# ESP32-S3_module.net
KiCad netlist of a schematic drawn in Altium Designer
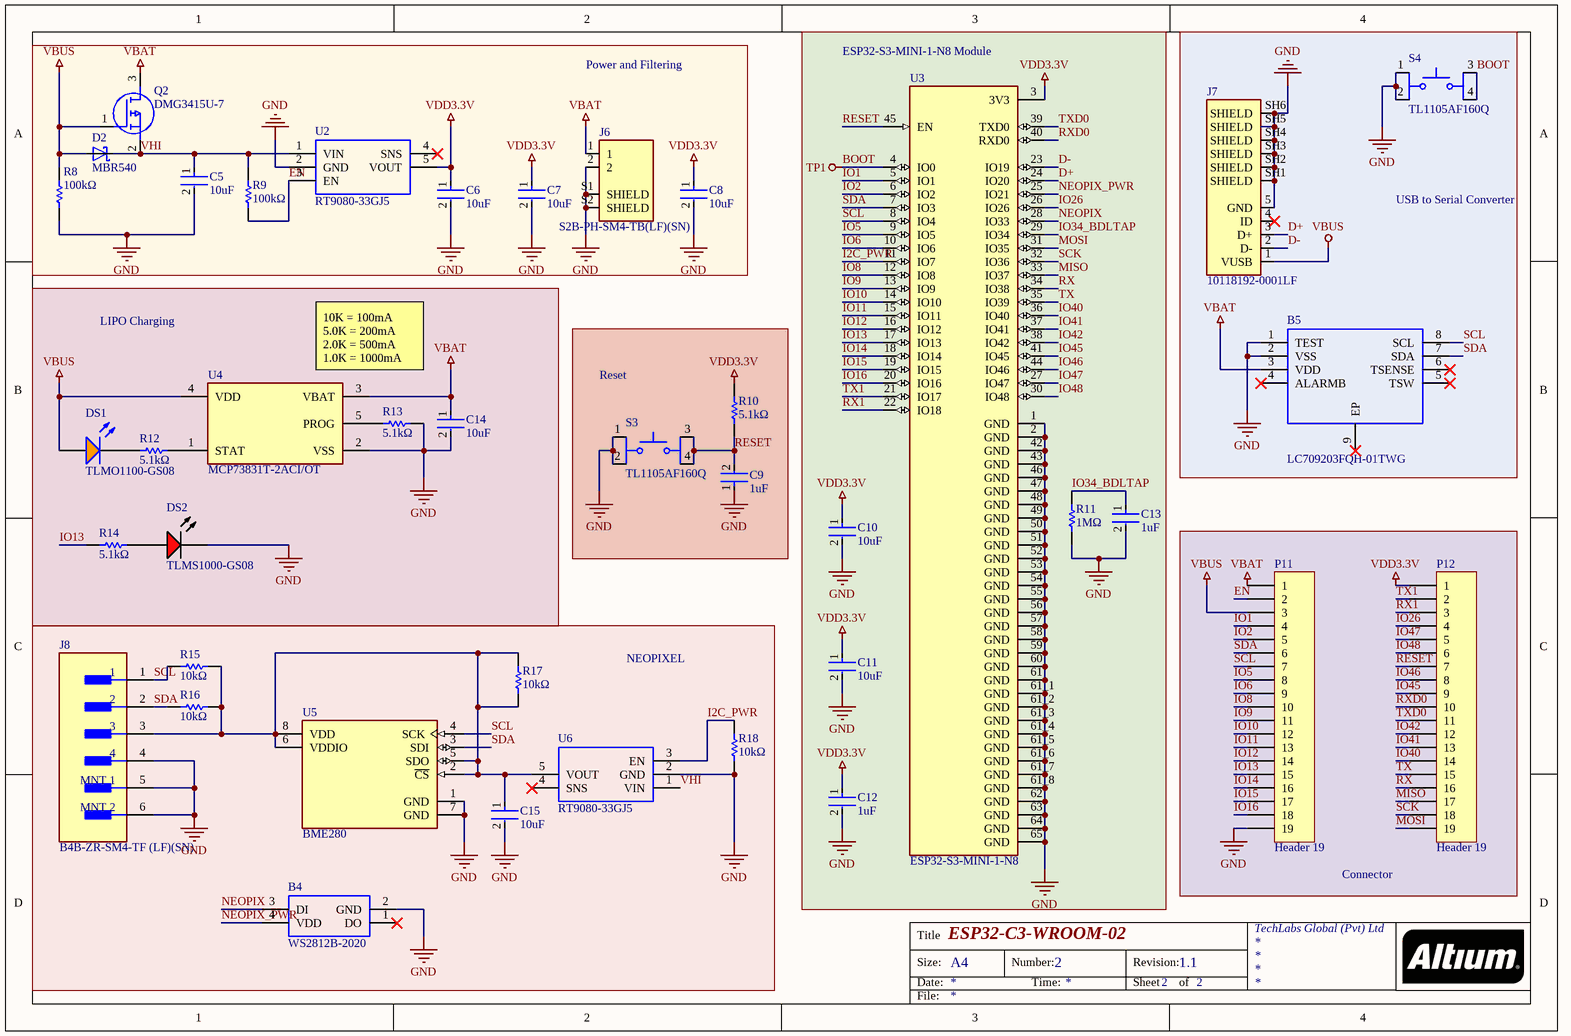
[diagram p0: ESP32-S3 module.SchDoc]

(export (version "E")
  (design (tool "Eeschema 10.0.6"))
  (components
    (comp (ref "B4")
      (value "WS2812B-2020")
      (footprint "WS2812B2020")
      (description "RGB SMD,2x2mm Light Emitting Diodes (LED) ROHS")
      (fields (field (name "MANUFACTURER") "Worldsemi") (field (name "LCSC PART#") "C965555"))
      (libsource (lib "WS2812B-2020") (part "WS2812B-2020"))
    )
    (comp (ref "B5")
      (value "LC709203FQH-01TWG")
      (footprint "SON65P400X300X80-9N")
      (description "DFN-8-EP(3x4) Battery Management ICs ROHS")
      (fields (field (name "MANUFACTURER") "onsemi") (field (name "LCSC PART#") "C152311"))
      (libsource (lib "LC709203FQH-01TWG") (part "LC709203FQH-01TWG"))
    )
    (comp (ref "C5")
      (value "10uF")
      (footprint "FP-CL10-IPC_C")
      (description "X5R 25V 10uF ±20% 0603 Multilayer Ceramic Capacitors MLCC - SMD/SMT ROHS")
      (fields (field (name "MFR. PART #") "CL10A106MA8NRNC") (field (name "LCSC PART #") "C96446"))
      (libsource (lib "Altium Content Vault") (part "b4654b650e69147ec39a6b967a45e02"))
    )
    (comp (ref "C6")
      (value "10uF")
      (footprint "FP-CL10-IPC_C")
      (description "X5R 25V 10uF ±20% 0603 Multilayer Ceramic Capacitors MLCC - SMD/SMT ROHS")
      (fields (field (name "MFR. PART #") "CL10A106MA8NRNC") (field (name "LCSC PART #") "C96446"))
      (libsource (lib "Altium Content Vault") (part "b4654b650e69147ec39a6b967a45e02"))
    )
    (comp (ref "C7")
      (value "10uF")
      (footprint "FP-CL10-IPC_C")
      (description "X5R 25V 10uF ±20% 0603 Multilayer Ceramic Capacitors MLCC - SMD/SMT ROHS")
      (fields (field (name "MFR. PART #") "CL10A106MA8NRNC") (field (name "LCSC PART #") "C96446"))
      (libsource (lib "Altium Content Vault") (part "b4654b650e69147ec39a6b967a45e02"))
    )
    (comp (ref "C8")
      (value "10uF")
      (footprint "FP-CL10-IPC_C")
      (description "X5R 25V 10uF ±20% 0603 Multilayer Ceramic Capacitors MLCC - SMD/SMT ROHS")
      (fields (field (name "MFR. PART #") "CL10A106MA8NRNC") (field (name "LCSC PART #") "C96446"))
      (libsource (lib "Altium Content Vault") (part "b4654b650e69147ec39a6b967a45e02"))
    )
    (comp (ref "C9")
      (value "1uF")
      (footprint "FP-CL10-IPC_A")
      (description "X5R 1uF 16V ±10% 0603 Multilayer Ceramic Capacitors MLCC - SMD/SMT ROHS")
      (fields (field (name "MANUFACTURER") "Samsung Electro-Mechanics") (field (name "LCSC PART #") "C1592"))
      (libsource (lib "Altium Content Vault") (part "b4654b650e69147ec39a6b967a45e02"))
    )
    (comp (ref "C10")
      (value "10uF")
      (footprint "FP-CL10-IPC_C")
      (description "X5R 25V 10uF ±20% 0603 Multilayer Ceramic Capacitors MLCC - SMD/SMT ROHS")
      (fields (field (name "MFR. PART #") "CL10A106MA8NRNC") (field (name "LCSC PART #") "C96446"))
      (libsource (lib "Altium Content Vault") (part "b4654b650e69147ec39a6b967a45e02"))
    )
    (comp (ref "C11")
      (value "10uF")
      (footprint "FP-CL10-IPC_C")
      (description "X5R 25V 10uF ±20% 0603 Multilayer Ceramic Capacitors MLCC - SMD/SMT ROHS")
      (fields (field (name "MFR. PART #") "CL10A106MA8NRNC") (field (name "LCSC PART #") "C96446"))
      (libsource (lib "Altium Content Vault") (part "b4654b650e69147ec39a6b967a45e02"))
    )
    (comp (ref "C12")
      (value "1uF")
      (footprint "FP-CL10-IPC_A")
      (description "X5R 1uF 16V ±10% 0603 Multilayer Ceramic Capacitors MLCC - SMD/SMT ROHS")
      (fields (field (name "LCSC PART #") "C1592") (field (name "MFR. PART #") "CL10A105KO8NNNC"))
      (libsource (lib "Altium Content Vault") (part "b4654b650e69147ec39a6b967a45e02"))
    )
    (comp (ref "C13")
      (value "1uF")
      (footprint "FP-CL10-IPC_A")
      (description "X5R 1uF 16V ±10% 0603 Multilayer Ceramic Capacitors MLCC - SMD/SMT ROHS")
      (fields (field (name "LCSC PART #") "C1592") (field (name "MFR. PART #") "CL10A105KO8NNNC"))
      (libsource (lib "Altium Content Vault") (part "b4654b650e69147ec39a6b967a45e02"))
    )
    (comp (ref "C14")
      (value "10uF")
      (footprint "FP-CL10-IPC_C")
      (description "X5R 25V 10uF ±20% 0603 Multilayer Ceramic Capacitors MLCC - SMD/SMT ROHS")
      (fields (field (name "MFR. PART #") "CL10A106MA8NRNC") (field (name "LCSC PART #") "C96446"))
      (libsource (lib "Altium Content Vault") (part "b4654b650e69147ec39a6b967a45e02"))
    )
    (comp (ref "C15")
      (value "10uF")
      (footprint "FP-CL10-IPC_C")
      (description "X5R 25V 10uF ±20% 0603 Multilayer Ceramic Capacitors MLCC - SMD/SMT ROHS")
      (fields (field (name "MFR. PART #") "CL10A106MA8NRNC") (field (name "LCSC PART #") "C96446"))
      (libsource (lib "Altium Content Vault") (part "b4654b650e69147ec39a6b967a45e02"))
    )
    (comp (ref "D2")
      (value "MBR540")
      (footprint "DIOAD2120W130L950D530P:DIOAD2120W130L950D530P")
      (description "40V 5A 580mV@5A DO-201AD Schottky Barrier Diodes (SBD) ROHS")
      (fields
        (field (name "MANUFACTURER") "Jilin Sino-Microelectronics")
        (field (name "LCSC PART #") "C272410")
      )
      (libsource (lib "MBR540-DO-201AD") (part "MBR540-DO-201AD"))
    )
    (comp (ref "DS1")
      (value "TLMO1100-GS08")
      (footprint "VISH-TLMX1100-2_V")
      (description "0603 Light Emitting Diodes (LED) ROHS")
      (fields (field (name "MANUFACTURER") "Vishay Intertech") (field (name "LCSC PART #") "C3148192"))
      (libsource (lib "Altium Content Vault") (part "LED-ORANGE-AK-2"))
    )
    (comp (ref "DS2")
      (value "TLMS1000-GS08")
      (footprint "VISH-TLMS1000_V")
      (description "Red 0603 Light Emitting Diodes (LED) ROHS")
      (fields (field (name "LCSC PART #") "C241893") (field (name "MANUFACTURER") "Vishay Intertech"))
      (libsource (lib "Altium Content Vault") (part "LED-RED-AK-2"))
    )
    (comp (ref "J6")
      (value "S2B-PH-SM4-TB(LF)(SN)")
      (footprint "JST_S2B-PH-SM4-TB(LF)(SN)")
      (fields (field (name "MANUFACTURER") "JST Sales America") (field (name "LCSC PART #") "C295747"))
      (libsource (lib "S2B-PH-SM4-TB(LF)(SN)") (part "S2B-PH-SM4-TB(LF)(SN)"))
    )
    (comp (ref "J7")
      (value "10118192-0001LF")
      (footprint "AMPHENOL_10118192-0001LF")
      (description "Single Port 5 Contact Horizontal Right Angle Shielded Micro B USB 2.0 Connector")
      (fields (field (name "LCSC PART #") "C132564") (field (name "MANUFACTURER") "Amphenol ICC"))
      (libsource (lib "10118192-0001LF") (part "10118192-0001LF"))
    )
    (comp (ref "J8")
      (value "B4B-ZR-SM4-TF (LF)(SN)")
      (footprint "FP-B4B-ZR-SM4-TF_LF_SN-MFG")
      (description "1x4P 1 1.5mm 4 Brass SMD,P=1.5mm Wire To Board / Wire To Wire Connector ROHS")
      (fields
        (field (name "MANUFACTURER") "JST Sales America")
        (field (name "MFR. PART #") "B4B-ZR-SM4-TF(LF)(SN)")
      )
      (libsource (lib "Altium Content Vault") (part "8e3688c4b118bffc0dd9b7401e414ba"))
    )
    (comp (ref "P11")
      (value "Header 19")
      (footprint "HDR1X19")
      (description "Header, 19-Pin")
      (fields (field (name "PUBLISHER") "Altium Limited"))
      (libsource (lib "Miscellaneous Connectors") (part "Header 19"))
    )
    (comp (ref "P12")
      (value "Header 19")
      (footprint "HDR1X19")
      (description "Header, 19-Pin")
      (fields (field (name "PUBLISHER") "Altium Limited"))
      (libsource (lib "Miscellaneous Connectors") (part "Header 19"))
    )
    (comp (ref "Q2")
      (value "DMG3415U-7")
      (footprint "SOT96P240X120-3N")
      (description "20V 4A 39mΩ@4.5V,4A 900mW P Channel SOT-23 MOSFETs ROHS")
      (fields (field (name "MANUFACTURER") "Diodes Incorporated") (field (name "LCSC PART#") "C96616"))
      (libsource (lib "DMG3415U-7") (part "DMG3415U-7"))
    )
    (comp (ref "R8")
      (value "100kΩ")
      (footprint "RESC1005X40X25NL05T10")
      (description "62.5mW 100kΩ ±1% Thick Film Resistors 0402 Chip Resistor - Surface Mount ROHS")
      (fields (field (name "MFR.PART #") "RC0402FR-07100KL") (field (name "MANUFACTURER") "YAGEO"))
      (libsource (lib "Altium Content Vault") (part "RES"))
    )
    (comp (ref "R9")
      (value "100kΩ")
      (footprint "RESC1005X40X25NL05T10")
      (description "62.5mW 100kΩ ±1% Thick Film Resistors 0402 Chip Resistor - Surface Mount ROHS")
      (fields (field (name "MFR.PART #") "RC0402FR-07100KL") (field (name "MANUFACTURER") "YAGEO"))
      (libsource (lib "Altium Content Vault") (part "RES"))
    )
    (comp (ref "R10")
      (value "5.1kΩ")
      (footprint "RESC1005X40X25NL05T10")
      (description "62.5mW Thick Film Resistors ±1% 5.1kΩ 0402 Chip Resistor - Surface Mount ROHS")
      (fields (field (name "MFR. PART #") "RC0402FR-075K1L") (field (name "MANUFACTURER") "YAGEO"))
      (libsource (lib "Altium Content Vault") (part "RES"))
    )
    (comp (ref "R11")
      (value "1MΩ")
      (footprint "RESC1005X40X25NL05T10")
      (description "62.5mW Thick Film Resistors ±1% 1MΩ 0402 Chip Resistor - Surface Mount ROHS")
      (fields (field (name "MFR. PART #") "RC0402FR-071ML") (field (name "LCSC PART #") "C138033"))
      (libsource (lib "Altium Content Vault") (part "RES"))
    )
    (comp (ref "R12")
      (value "5.1kΩ")
      (footprint "RESC1005X40X25NL05T10")
      (description "62.5mW Thick Film Resistors ±1% 5.1kΩ 0402 Chip Resistor - Surface Mount ROHS")
      (fields (field (name "MFR. PART #") "RC0402FR-075K1L") (field (name "MANUFACTURER") "YAGEO"))
      (libsource (lib "Altium Content Vault") (part "RES"))
    )
    (comp (ref "R13")
      (value "5.1kΩ")
      (footprint "RESC1005X40X25NL05T10")
      (description "62.5mW Thick Film Resistors ±1% 5.1kΩ 0402 Chip Resistor - Surface Mount ROHS")
      (fields (field (name "MFR. PART #") "RC0402FR-075K1L") (field (name "MANUFACTURER") "YAGEO"))
      (libsource (lib "Altium Content Vault") (part "RES"))
    )
    (comp (ref "R14")
      (value "5.1kΩ")
      (footprint "RESC1005X40X25NL05T10")
      (description "62.5mW Thick Film Resistors ±1% 5.1kΩ 0402 Chip Resistor - Surface Mount ROHS")
      (fields (field (name "MFR. PART #") "RC0402FR-075K1L") (field (name "MANUFACTURER") "YAGEO"))
      (libsource (lib "Altium Content Vault") (part "RES"))
    )
    (comp (ref "R15")
      (value "10kΩ")
      (footprint "RESC1005X40X25LL05T10")
      (description "10kΩ Thick Film Resistors 62.5mW ±1% 0402 Chip Resistor - Surface Mount ROHS")
      (fields (field (name "MFR. PART #") "RC0402FR-0710KL") (field (name "MANUFACTURER") "YAGEO"))
      (libsource (lib "Altium Content Vault") (part "RES"))
    )
    (comp (ref "R16")
      (value "10kΩ")
      (footprint "RESC1005X40X25LL05T10")
      (description "10kΩ Thick Film Resistors 62.5mW ±1% 0402 Chip Resistor - Surface Mount ROHS")
      (fields (field (name "MFR. PART #") "RC0402FR-0710KL") (field (name "MANUFACTURER") "YAGEO"))
      (libsource (lib "Altium Content Vault") (part "RES"))
    )
    (comp (ref "R17")
      (value "10kΩ")
      (footprint "RESC1005X40X25LL05T10")
      (description "10kΩ Thick Film Resistors 62.5mW ±1% 0402 Chip Resistor - Surface Mount ROHS")
      (fields (field (name "MFR. PART #") "RC0402FR-0710KL") (field (name "MANUFACTURER") "YAGEO"))
      (libsource (lib "Altium Content Vault") (part "RES"))
    )
    (comp (ref "R18")
      (value "10kΩ")
      (footprint "RESC1005X40X25LL05T10")
      (description "10kΩ Thick Film Resistors 62.5mW ±1% 0402 Chip Resistor - Surface Mount ROHS")
      (fields (field (name "MFR. PART #") "RC0402FR-0710KL") (field (name "MANUFACTURER") "YAGEO"))
      (libsource (lib "Altium Content Vault") (part "RES"))
    )
    (comp (ref "S3")
      (value "TL1105AF160Q")
      (footprint "TL1105AF160Q")
      (description "6mm 1.4mm Round Button 50mA Straight 6mm SPST 12V Plugin,6x6mm Tactile Switches ROHS")
      (fields (field (name "MANUFACTURER") "E-Switch") (field (name "LCSC PART #") "C273465"))
      (libsource (lib "TL1105AF160Q") (part "TL1105AF160Q"))
    )
    (comp (ref "S4")
      (value "TL1105AF160Q")
      (footprint "TL1105AF160Q")
      (description "6mm 1.4mm Round Button 50mA Straight 6mm SPST 12V Plugin,6x6mm Tactile Switches ROHS")
      (fields (field (name "MANUFACTURER") "E-Switch") (field (name "LCSC PART #") "C273465"))
      (libsource (lib "TL1105AF160Q") (part "TL1105AF160Q"))
    )
    (comp (ref "U2")
      (value "RT9080-33GJ5")
      (footprint "SOT94P280X100-5N")
      (description "TSOT-23-5 Linear Voltage Regulators (LDO) ROHS")
      (fields (field (name "MANUFACTURER") "Richtek Tech") (field (name "LCSC PART#") "C841192"))
      (libsource (lib "RT9080-33GJ5") (part "RT9080-33GJ5"))
    )
    (comp (ref "U3")
      (value "ESP32-S3-MINI-1-N8")
      (footprint "XCVR_ESP32-S3-MINI-1-N8")
      (description "Bluetooth, WiFi 802.11b/g/n, Bluetooth v5.0 Transceiver Module 2.4GHz PCB Trace Surface Mount")
      (fields (field (name "MANUFACTURER") "Espressif Systems") (field (name "LCSC PART #") "C2913206"))
      (libsource (lib "ESP32-S3-MINI-1-N8") (part "U?"))
    )
    (comp (ref "U4")
      (value "MCP73831T-2ACI/OT")
      (footprint "FP-C04-091-OT-IPC_B")
      (description "SOT-23-5 Battery Management ICs ROHS")
      (fields (field (name "LCSC PART #") "C424093") (field (name "MANUFACTURER") "Microchip Tech"))
      (libsource (lib "Altium Content Vault") (part "61f5a3bb3429d9e0caadea342aa3b19"))
    )
    (comp (ref "U5")
      (value "BME280")
      (footprint "FP-BME280-MFG")
      (description "LGA-8 Temperature and Humidity Sensor ROHS")
      (fields (field (name "LCSC PART #") "C92489") (field (name "MANUFACTURER") "Bosch Sensortec"))
      (libsource (lib "Altium Content Vault") (part "d58e2f6669bc67e6a2bc6a28610ca79"))
    )
    (comp (ref "U6")
      (value "RT9080-33GJ5")
      (footprint "SOT94P280X100-5N")
      (description "TSOT-23-5 Linear Voltage Regulators (LDO) ROHS")
      (fields (field (name "MANUFACTURER") "Richtek Tech") (field (name "LCSC PART#") "C841192"))
      (libsource (lib "RT9080-33GJ5") (part "RT9080-33GJ5"))
    )
  )
  (nets
    (net (code "1") (name "/D+") (class "Default")
      (node (ref "J7") (pin "3") (pinfunction "D+_3") (pintype "passive"))
      (node (ref "U3") (pin "24") (pinfunction "IO20_24") (pintype "bidirectional"))
    )
    (net (code "2") (name "/D-") (class "Default")
      (node (ref "J7") (pin "2") (pinfunction "D-_2") (pintype "passive"))
      (node (ref "U3") (pin "23") (pinfunction "IO19_23") (pintype "bidirectional"))
    )
    (net (code "3") (name "/EN") (class "Default")
      (node (ref "P11") (pin "2") (pinfunction "2_2") (pintype "passive"))
      (node (ref "R9") (pin "2") (pinfunction "2_2") (pintype "passive"))
      (node (ref "U2") (pin "3") (pinfunction "EN_3") (pintype "passive"))
    )
    (net (code "4") (name "/I2C_PWR") (class "Default")
      (node (ref "R18") (pin "2") (pinfunction "2_2") (pintype "passive"))
      (node (ref "U3") (pin "11") (pinfunction "IO7_11") (pintype "bidirectional"))
      (node (ref "U6") (pin "3") (pinfunction "EN_3") (pintype "passive"))
    )
    (net (code "5") (name "/IO1") (class "Default")
      (node (ref "P11") (pin "4") (pinfunction "4_4") (pintype "passive"))
      (node (ref "U3") (pin "5") (pinfunction "IO1_5") (pintype "bidirectional"))
    )
    (net (code "6") (name "/IO2") (class "Default")
      (node (ref "P11") (pin "5") (pinfunction "5_5") (pintype "passive"))
      (node (ref "U3") (pin "6") (pinfunction "IO2_6") (pintype "bidirectional"))
    )
    (net (code "7") (name "/IO5") (class "Default")
      (node (ref "P11") (pin "8") (pinfunction "8_8") (pintype "passive"))
      (node (ref "U3") (pin "9") (pinfunction "IO5_9") (pintype "bidirectional"))
    )
    (net (code "8") (name "/IO6") (class "Default")
      (node (ref "P11") (pin "9") (pinfunction "9_9") (pintype "passive"))
      (node (ref "U3") (pin "10") (pinfunction "IO6_10") (pintype "bidirectional"))
    )
    (net (code "9") (name "/IO8") (class "Default")
      (node (ref "P11") (pin "10") (pinfunction "10_10") (pintype "passive"))
      (node (ref "U3") (pin "12") (pinfunction "IO8_12") (pintype "bidirectional"))
    )
    (net (code "10") (name "/IO9") (class "Default")
      (node (ref "P11") (pin "11") (pinfunction "11_11") (pintype "passive"))
      (node (ref "U3") (pin "13") (pinfunction "IO9_13") (pintype "bidirectional"))
    )
    (net (code "11") (name "/IO10") (class "Default")
      (node (ref "P11") (pin "12") (pinfunction "12_12") (pintype "passive"))
      (node (ref "U3") (pin "14") (pinfunction "IO10_14") (pintype "bidirectional"))
    )
    (net (code "12") (name "/IO11") (class "Default")
      (node (ref "P11") (pin "13") (pinfunction "13_13") (pintype "passive"))
      (node (ref "U3") (pin "15") (pinfunction "IO11_15") (pintype "bidirectional"))
    )
    (net (code "13") (name "/IO12") (class "Default")
      (node (ref "P11") (pin "14") (pinfunction "14_14") (pintype "passive"))
      (node (ref "U3") (pin "16") (pinfunction "IO12_16") (pintype "bidirectional"))
    )
    (net (code "14") (name "/IO13") (class "Default")
      (node (ref "P11") (pin "15") (pinfunction "15_15") (pintype "passive"))
      (node (ref "R14") (pin "2") (pinfunction "2_2") (pintype "passive"))
      (node (ref "U3") (pin "17") (pinfunction "IO13_17") (pintype "bidirectional"))
    )
    (net (code "15") (name "/IO14") (class "Default")
      (node (ref "P11") (pin "16") (pinfunction "16_16") (pintype "passive"))
      (node (ref "U3") (pin "18") (pinfunction "IO14_18") (pintype "bidirectional"))
    )
    (net (code "16") (name "/IO15") (class "Default")
      (node (ref "P11") (pin "17") (pinfunction "17_17") (pintype "passive"))
      (node (ref "U3") (pin "19") (pinfunction "IO15_19") (pintype "bidirectional"))
    )
    (net (code "17") (name "/IO16") (class "Default")
      (node (ref "P11") (pin "18") (pinfunction "18_18") (pintype "passive"))
      (node (ref "U3") (pin "20") (pinfunction "IO16_20") (pintype "bidirectional"))
    )
    (net (code "18") (name "/IO26") (class "Default")
      (node (ref "P12") (pin "4") (pinfunction "4_4") (pintype "passive"))
      (node (ref "U3") (pin "26") (pinfunction "IO26_26") (pintype "bidirectional"))
    )
    (net (code "19") (name "/IO34_BDLTAP") (class "Default")
      (node (ref "C13") (pin "1") (pinfunction "1_1") (pintype "passive"))
      (node (ref "R11") (pin "2") (pinfunction "2_2") (pintype "passive"))
      (node (ref "U3") (pin "29") (pinfunction "IO34_29") (pintype "bidirectional"))
    )
    (net (code "20") (name "/IO40") (class "Default")
      (node (ref "P12") (pin "14") (pinfunction "14_14") (pintype "passive"))
      (node (ref "U3") (pin "36") (pinfunction "IO40_36") (pintype "bidirectional"))
    )
    (net (code "21") (name "/IO41") (class "Default")
      (node (ref "P12") (pin "13") (pinfunction "13_13") (pintype "passive"))
      (node (ref "U3") (pin "37") (pinfunction "IO41_37") (pintype "bidirectional"))
    )
    (net (code "22") (name "/IO42") (class "Default")
      (node (ref "P12") (pin "12") (pinfunction "12_12") (pintype "passive"))
      (node (ref "U3") (pin "38") (pinfunction "IO42_38") (pintype "bidirectional"))
    )
    (net (code "23") (name "/IO45") (class "Default")
      (node (ref "P12") (pin "9") (pinfunction "9_9") (pintype "passive"))
      (node (ref "U3") (pin "41") (pinfunction "IO45_41") (pintype "bidirectional"))
    )
    (net (code "24") (name "/IO46") (class "Default")
      (node (ref "P12") (pin "8") (pinfunction "8_8") (pintype "passive"))
      (node (ref "U3") (pin "44") (pinfunction "IO46_44") (pintype "bidirectional"))
    )
    (net (code "25") (name "/IO47") (class "Default")
      (node (ref "P12") (pin "5") (pinfunction "5_5") (pintype "passive"))
      (node (ref "U3") (pin "27") (pinfunction "IO47_27") (pintype "bidirectional"))
    )
    (net (code "26") (name "/IO48") (class "Default")
      (node (ref "P12") (pin "6") (pinfunction "6_6") (pintype "passive"))
      (node (ref "U3") (pin "30") (pinfunction "IO48_30") (pintype "bidirectional"))
    )
    (net (code "27") (name "/MISO") (class "Default")
      (node (ref "P12") (pin "17") (pinfunction "17_17") (pintype "passive"))
      (node (ref "U3") (pin "33") (pinfunction "IO37_33") (pintype "bidirectional"))
    )
    (net (code "28") (name "/MOSI") (class "Default")
      (node (ref "P12") (pin "19") (pinfunction "19_19") (pintype "passive"))
      (node (ref "U3") (pin "31") (pinfunction "IO35_31") (pintype "bidirectional"))
    )
    (net (code "29") (name "/NEOPIX") (class "Default")
      (node (ref "B4") (pin "3") (pinfunction "DI_3") (pintype "passive"))
      (node (ref "U3") (pin "28") (pinfunction "IO33_28") (pintype "bidirectional"))
    )
    (net (code "30") (name "/NEOPIX_PWR") (class "Default")
      (node (ref "B4") (pin "4") (pinfunction "VDD_4") (pintype "passive"))
      (node (ref "U3") (pin "25") (pinfunction "IO21_25") (pintype "bidirectional"))
    )
    (net (code "31") (name "/RESET") (class "Default")
      (node (ref "C9") (pin "2") (pinfunction "2_2") (pintype "passive"))
      (node (ref "P12") (pin "7") (pinfunction "7_7") (pintype "passive"))
      (node (ref "R10") (pin "1") (pinfunction "1_1") (pintype "passive"))
      (node (ref "S3") (pin "3") (pinfunction "3_3") (pintype "passive"))
      (node (ref "S3") (pin "4") (pinfunction "4_4") (pintype "passive"))
      (node (ref "U3") (pin "45") (pinfunction "EN_45") (pintype "input"))
    )
    (net (code "32") (name "/RX") (class "Default")
      (node (ref "P12") (pin "16") (pinfunction "16_16") (pintype "passive"))
      (node (ref "U3") (pin "34") (pinfunction "IO38_34") (pintype "bidirectional"))
    )
    (net (code "33") (name "/RX1") (class "Default")
      (node (ref "P12") (pin "3") (pinfunction "3_3") (pintype "passive"))
      (node (ref "U3") (pin "22") (pinfunction "IO18_22") (pintype "bidirectional"))
    )
    (net (code "34") (name "/RXD0") (class "Default")
      (node (ref "P12") (pin "10") (pinfunction "10_10") (pintype "passive"))
      (node (ref "U3") (pin "40") (pinfunction "RXD0_40") (pintype "bidirectional"))
    )
    (net (code "35") (name "/SCK") (class "Default")
      (node (ref "P12") (pin "18") (pinfunction "18_18") (pintype "passive"))
      (node (ref "U3") (pin "32") (pinfunction "IO36_32") (pintype "bidirectional"))
    )
    (net (code "36") (name "/SCL") (class "Default")
      (node (ref "B5") (pin "8") (pinfunction "SCL_8") (pintype "passive"))
      (node (ref "J8") (pin "1") (pinfunction "1_1") (pintype "passive"))
      (node (ref "P11") (pin "7") (pinfunction "7_7") (pintype "passive"))
      (node (ref "R15") (pin "2") (pinfunction "2_2") (pintype "passive"))
      (node (ref "U3") (pin "8") (pinfunction "IO4_8") (pintype "bidirectional"))
      (node (ref "U5") (pin "4") (pinfunction "SCK_4") (pintype "input"))
    )
    (net (code "37") (name "/SDA") (class "Default")
      (node (ref "B5") (pin "7") (pinfunction "SDA_7") (pintype "passive"))
      (node (ref "J8") (pin "2") (pinfunction "2_2") (pintype "passive"))
      (node (ref "P11") (pin "6") (pinfunction "6_6") (pintype "passive"))
      (node (ref "R16") (pin "2") (pinfunction "2_2") (pintype "passive"))
      (node (ref "U3") (pin "7") (pinfunction "IO3_7") (pintype "bidirectional"))
      (node (ref "U5") (pin "3") (pinfunction "SDI_3") (pintype "bidirectional"))
    )
    (net (code "38") (name "/TX") (class "Default")
      (node (ref "P12") (pin "15") (pinfunction "15_15") (pintype "passive"))
      (node (ref "U3") (pin "35") (pinfunction "IO39_35") (pintype "bidirectional"))
    )
    (net (code "39") (name "/TX1") (class "Default")
      (node (ref "P12") (pin "2") (pinfunction "2_2") (pintype "passive"))
      (node (ref "U3") (pin "21") (pinfunction "IO17_21") (pintype "bidirectional"))
    )
    (net (code "40") (name "/TXD0") (class "Default")
      (node (ref "P12") (pin "11") (pinfunction "11_11") (pintype "passive"))
      (node (ref "U3") (pin "39") (pinfunction "TXD0_39") (pintype "bidirectional"))
    )
    (net (code "41") (name "/VHI") (class "Default")
      (node (ref "C5") (pin "1") (pinfunction "1_1") (pintype "passive"))
      (node (ref "D2") (pin "C") (pinfunction "C_C") (pintype "passive"))
      (node (ref "Q2") (pin "2") (pinfunction "S_2") (pintype "passive"))
      (node (ref "R9") (pin "1") (pinfunction "1_1") (pintype "passive"))
      (node (ref "U2") (pin "1") (pinfunction "VIN_1") (pintype "passive"))
      (node (ref "U6") (pin "1") (pinfunction "VIN_1") (pintype "passive"))
    )
    (net (code "42") (name "GND") (class "Default")
      (node (ref "B4") (pin "2") (pinfunction "GND_2") (pintype "passive"))
      (node (ref "B5") (pin "1") (pinfunction "TEST_1") (pintype "passive"))
      (node (ref "B5") (pin "2") (pinfunction "VSS_2") (pintype "passive"))
      (node (ref "C10") (pin "2") (pinfunction "2_2") (pintype "passive"))
      (node (ref "C11") (pin "2") (pinfunction "2_2") (pintype "passive"))
      (node (ref "C12") (pin "2") (pinfunction "2_2") (pintype "passive"))
      (node (ref "C13") (pin "2") (pinfunction "2_2") (pintype "passive"))
      (node (ref "C14") (pin "2") (pinfunction "2_2") (pintype "passive"))
      (node (ref "C15") (pin "2") (pinfunction "2_2") (pintype "passive"))
      (node (ref "C5") (pin "2") (pinfunction "2_2") (pintype "passive"))
      (node (ref "C6") (pin "2") (pinfunction "2_2") (pintype "passive"))
      (node (ref "C7") (pin "2") (pinfunction "2_2") (pintype "passive"))
      (node (ref "C8") (pin "2") (pinfunction "2_2") (pintype "passive"))
      (node (ref "C9") (pin "1") (pinfunction "1_1") (pintype "passive"))
      (node (ref "DS2") (pin "2") (pinfunction "K_2") (pintype "passive"))
      (node (ref "J6") (pin "2") (pinfunction "2_2") (pintype "passive"))
      (node (ref "J6") (pin "S1") (pinfunction "SHIELD_S1") (pintype "passive"))
      (node (ref "J6") (pin "S2") (pinfunction "SHIELD_S2") (pintype "passive"))
      (node (ref "J7") (pin "5") (pinfunction "GND_5") (pintype "passive"))
      (node (ref "J7") (pin "SH1") (pinfunction "SHIELD_SH1") (pintype "passive"))
      (node (ref "J7") (pin "SH2") (pinfunction "SHIELD_SH2") (pintype "passive"))
      (node (ref "J7") (pin "SH3") (pinfunction "SHIELD_SH3") (pintype "passive"))
      (node (ref "J7") (pin "SH4") (pinfunction "SHIELD_SH4") (pintype "passive"))
      (node (ref "J7") (pin "SH5") (pinfunction "SHIELD_SH5") (pintype "passive"))
      (node (ref "J7") (pin "SH6") (pinfunction "SHIELD_SH6") (pintype "passive"))
      (node (ref "J8") (pin "4") (pinfunction "4_4") (pintype "passive"))
      (node (ref "J8") (pin "5") (pinfunction "MNT_1_5") (pintype "passive"))
      (node (ref "J8") (pin "6") (pinfunction "MNT_2_6") (pintype "passive"))
      (node (ref "P11") (pin "19") (pinfunction "19_19") (pintype "passive"))
      (node (ref "R11") (pin "1") (pinfunction "1_1") (pintype "passive"))
      (node (ref "R13") (pin "1") (pinfunction "1_1") (pintype "passive"))
      (node (ref "R18") (pin "1") (pinfunction "1_1") (pintype "passive"))
      (node (ref "R8") (pin "1") (pinfunction "1_1") (pintype "passive"))
      (node (ref "S3") (pin "1") (pinfunction "1_1") (pintype "passive"))
      (node (ref "S3") (pin "2") (pinfunction "2_2") (pintype "passive"))
      (node (ref "S4") (pin "1") (pinfunction "1_1") (pintype "passive"))
      (node (ref "S4") (pin "2") (pinfunction "2_2") (pintype "passive"))
      (node (ref "U2") (pin "2") (pinfunction "GND_2") (pintype "passive"))
      (node (ref "U3") (pin "1") (pinfunction "GND_1") (pintype "power_in"))
      (node (ref "U3") (pin "2") (pinfunction "GND_2") (pintype "power_in"))
      (node (ref "U3") (pin "42") (pinfunction "GND_42") (pintype "power_in"))
      (node (ref "U3") (pin "43") (pinfunction "GND_43") (pintype "power_in"))
      (node (ref "U3") (pin "46") (pinfunction "GND_46") (pintype "power_in"))
      (node (ref "U3") (pin "47") (pinfunction "GND_47") (pintype "power_in"))
      (node (ref "U3") (pin "48") (pinfunction "GND_48") (pintype "power_in"))
      (node (ref "U3") (pin "49") (pinfunction "GND_49") (pintype "power_in"))
      (node (ref "U3") (pin "50") (pinfunction "GND_50") (pintype "power_in"))
      (node (ref "U3") (pin "51") (pinfunction "GND_51") (pintype "power_in"))
      (node (ref "U3") (pin "52") (pinfunction "GND_52") (pintype "power_in"))
      (node (ref "U3") (pin "53") (pinfunction "GND_53") (pintype "power_in"))
      (node (ref "U3") (pin "54") (pinfunction "GND_54") (pintype "power_in"))
      (node (ref "U3") (pin "55") (pinfunction "GND_55") (pintype "power_in"))
      (node (ref "U3") (pin "56") (pinfunction "GND_56") (pintype "power_in"))
      (node (ref "U3") (pin "57") (pinfunction "GND_57") (pintype "power_in"))
      (node (ref "U3") (pin "58") (pinfunction "GND_58") (pintype "power_in"))
      (node (ref "U3") (pin "59") (pinfunction "GND_59") (pintype "power_in"))
      (node (ref "U3") (pin "60") (pinfunction "GND_60") (pintype "power_in"))
      (node (ref "U3") (pin "61") (pinfunction "GND_61") (pintype "power_in"))
      (node (ref "U3") (pin "61_1") (pinfunction "GND_61_1") (pintype "power_in"))
      (node (ref "U3") (pin "61_2") (pinfunction "GND_61_2") (pintype "power_in"))
      (node (ref "U3") (pin "61_3") (pinfunction "GND_61_3") (pintype "power_in"))
      (node (ref "U3") (pin "61_4") (pinfunction "GND_61_4") (pintype "power_in"))
      (node (ref "U3") (pin "61_5") (pinfunction "GND_61_5") (pintype "power_in"))
      (node (ref "U3") (pin "61_6") (pinfunction "GND_61_6") (pintype "power_in"))
      (node (ref "U3") (pin "61_7") (pinfunction "GND_61_7") (pintype "power_in"))
      (node (ref "U3") (pin "61_8") (pinfunction "GND_61_8") (pintype "power_in"))
      (node (ref "U3") (pin "62") (pinfunction "GND_62") (pintype "power_in"))
      (node (ref "U3") (pin "63") (pinfunction "GND_63") (pintype "power_in"))
      (node (ref "U3") (pin "64") (pinfunction "GND_64") (pintype "power_in"))
      (node (ref "U3") (pin "65") (pinfunction "GND_65") (pintype "power_in"))
      (node (ref "U4") (pin "2") (pinfunction "VSS_2") (pintype "power_in"))
      (node (ref "U5") (pin "1") (pinfunction "GND_1") (pintype "power_in"))
      (node (ref "U5") (pin "7") (pinfunction "GND_7") (pintype "power_in"))
      (node (ref "U6") (pin "2") (pinfunction "GND_2") (pintype "passive"))
    )
    (net (code "43") (name "Net-(DS1-K)") (class "Default")
      (node (ref "DS1") (pin "2") (pinfunction "K_2") (pintype "passive"))
      (node (ref "R12") (pin "2") (pinfunction "2_2") (pintype "passive"))
    )
    (net (code "44") (name "Net-(DS2-A)") (class "Default")
      (node (ref "DS2") (pin "1") (pinfunction "A_1") (pintype "passive"))
      (node (ref "R14") (pin "1") (pinfunction "1_1") (pintype "passive"))
    )
    (net (code "45") (name "Net-(U4-PROG)") (class "Default")
      (node (ref "R13") (pin "2") (pinfunction "2_2") (pintype "passive"))
      (node (ref "U4") (pin "5") (pinfunction "PROG_5") (pintype "passive"))
    )
    (net (code "46") (name "Net-(U4-STAT)") (class "Default")
      (node (ref "R12") (pin "1") (pinfunction "1_1") (pintype "passive"))
      (node (ref "U4") (pin "1") (pinfunction "STAT_1") (pintype "passive"))
    )
    (net (code "47") (name "Net-(U5-SDO)") (class "Default")
      (node (ref "C15") (pin "1") (pinfunction "1_1") (pintype "passive"))
      (node (ref "J8") (pin "3") (pinfunction "3_3") (pintype "passive"))
      (node (ref "R15") (pin "1") (pinfunction "1_1") (pintype "passive"))
      (node (ref "R16") (pin "1") (pinfunction "1_1") (pintype "passive"))
      (node (ref "R17") (pin "1") (pinfunction "1_1") (pintype "passive"))
      (node (ref "R17") (pin "2") (pinfunction "2_2") (pintype "passive"))
      (node (ref "U5") (pin "2") (pinfunction "~{CS}_2") (pintype "input"))
      (node (ref "U5") (pin "5") (pinfunction "SDO_5") (pintype "bidirectional"))
      (node (ref "U5") (pin "6") (pinfunction "VDDIO_6") (pintype "power_in"))
      (node (ref "U5") (pin "8") (pinfunction "VDD_8") (pintype "power_in"))
      (node (ref "U6") (pin "5") (pinfunction "VOUT_5") (pintype "passive"))
    )
    (net (code "48") (name "TP1") (class "Default")
      (node (ref "S4") (pin "3") (pinfunction "3_3") (pintype "passive"))
      (node (ref "S4") (pin "4") (pinfunction "4_4") (pintype "passive"))
      (node (ref "U3") (pin "4") (pinfunction "IO0_4") (pintype "bidirectional"))
    )
    (net (code "49") (name "VBAT") (class "Default")
      (node (ref "B5") (pin "3") (pinfunction "VDD_3") (pintype "passive"))
      (node (ref "C14") (pin "1") (pinfunction "1_1") (pintype "passive"))
      (node (ref "J6") (pin "1") (pinfunction "1_1") (pintype "passive"))
      (node (ref "P11") (pin "1") (pinfunction "1_1") (pintype "passive"))
      (node (ref "Q2") (pin "3") (pinfunction "D_3") (pintype "passive"))
      (node (ref "U4") (pin "3") (pinfunction "VBAT_3") (pintype "power_in"))
    )
    (net (code "50") (name "VBUS") (class "Default")
      (node (ref "D2") (pin "A") (pinfunction "A_A") (pintype "passive"))
      (node (ref "DS1") (pin "1") (pinfunction "A_1") (pintype "passive"))
      (node (ref "J7") (pin "1") (pinfunction "VUSB_1") (pintype "passive"))
      (node (ref "P11") (pin "3") (pinfunction "3_3") (pintype "passive"))
      (node (ref "Q2") (pin "1") (pinfunction "G_1") (pintype "passive"))
      (node (ref "R8") (pin "2") (pinfunction "2_2") (pintype "passive"))
      (node (ref "U4") (pin "4") (pinfunction "VDD_4") (pintype "power_in"))
    )
    (net (code "51") (name "VDD3.3V") (class "Default")
      (node (ref "C10") (pin "1") (pinfunction "1_1") (pintype "passive"))
      (node (ref "C11") (pin "1") (pinfunction "1_1") (pintype "passive"))
      (node (ref "C12") (pin "1") (pinfunction "1_1") (pintype "passive"))
      (node (ref "C6") (pin "1") (pinfunction "1_1") (pintype "passive"))
      (node (ref "C7") (pin "1") (pinfunction "1_1") (pintype "passive"))
      (node (ref "C8") (pin "1") (pinfunction "1_1") (pintype "passive"))
      (node (ref "P12") (pin "1") (pinfunction "1_1") (pintype "passive"))
      (node (ref "R10") (pin "2") (pinfunction "2_2") (pintype "passive"))
      (node (ref "U2") (pin "5") (pinfunction "VOUT_5") (pintype "passive"))
      (node (ref "U3") (pin "3") (pinfunction "3V3_3") (pintype "power_in"))
    )
    (net (code "52") (name "unconnected-(B4-DO-Pad1)") (class "Default")
      (node (ref "B4") (pin "1") (pinfunction "DO_1") (pintype "passive+no_connect"))
    )
    (net (code "53") (name "unconnected-(B5-ALARMB-Pad4)") (class "Default")
      (node (ref "B5") (pin "4") (pinfunction "ALARMB_4") (pintype "passive+no_connect"))
    )
    (net (code "54") (name "unconnected-(B5-EP-Pad9)") (class "Default")
      (node (ref "B5") (pin "9") (pinfunction "EP_9") (pintype "passive+no_connect"))
    )
    (net (code "55") (name "unconnected-(B5-TSENSE-Pad6)") (class "Default")
      (node (ref "B5") (pin "6") (pinfunction "TSENSE_6") (pintype "passive+no_connect"))
    )
    (net (code "56") (name "unconnected-(B5-TSW-Pad5)") (class "Default")
      (node (ref "B5") (pin "5") (pinfunction "TSW_5") (pintype "passive+no_connect"))
    )
    (net (code "57") (name "unconnected-(J7-ID-Pad4)") (class "Default")
      (node (ref "J7") (pin "4") (pinfunction "ID_4") (pintype "passive+no_connect"))
    )
    (net (code "58") (name "unconnected-(U2-SNS-Pad4)") (class "Default")
      (node (ref "U2") (pin "4") (pinfunction "SNS_4") (pintype "passive+no_connect"))
    )
    (net (code "59") (name "unconnected-(U6-SNS-Pad4)") (class "Default")
      (node (ref "U6") (pin "4") (pinfunction "SNS_4") (pintype "passive+no_connect"))
    )
  )
)
